# Sheet3.net
KiCad netlist of a schematic drawn in Altium Designer
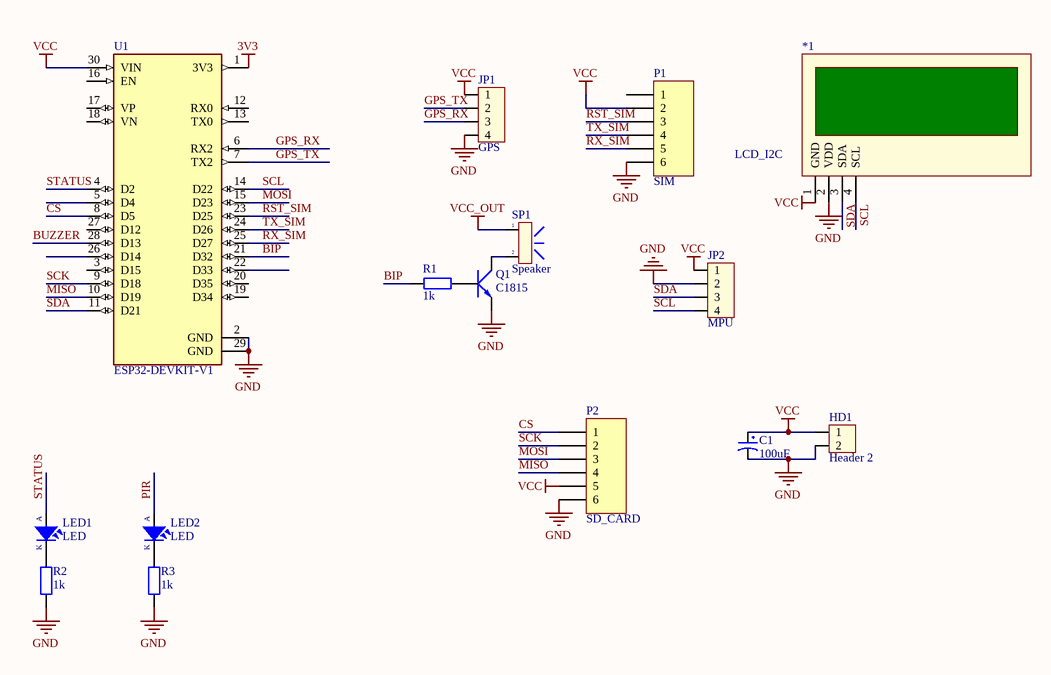
[diagram p0: Sheet3.SchDoc]

(export (version "E")
  (design (tool "Eeschema 10.0.6"))
  (components
    (comp (ref "*1")
      (value "LCD_I2C")
      (footprint "LCD_I2C_2004")
      (libsource (lib "LCD_i2c") (part "LCD_I2C"))
    )
    (comp (ref "C1")
      (value "100uF")
      (footprint "PART:CP1.5/3.4")
      (description "Cap 100uF/35V - 470uF/16V")
      (libsource (lib "PART") (part "CP3"))
    )
    (comp (ref "HD1")
      (value "Header 2")
      (footprint "PART:HED2")
      (description "Header 2 (Green)")
      (libsource (lib "PART") (part "Hed2"))
    )
    (comp (ref "JP1")
      (value "GPS")
      (footprint "CON4")
      (description "Connector 4")
      (libsource (lib "PART") (part "Con4"))
    )
    (comp (ref "JP2")
      (value "MPU")
      (footprint "CON4")
      (description "Connector 4")
      (libsource (lib "PART") (part "Con4"))
    )
    (comp (ref "LED1")
      (value "LED")
      (footprint "LED-5")
      (description "LED Single colour Green and Red")
      (libsource (lib "PART") (part "LED"))
    )
    (comp (ref "LED2")
      (value "LED")
      (footprint "LED-5")
      (description "LED Single colour Green and Red")
      (libsource (lib "PART") (part "LED"))
    )
    (comp (ref "P1")
      (value "SIM")
      (footprint "HDR1X6")
      (description "Header, 6-Pin")
      (fields (field (name "PUBLISHER") "Altium Limited"))
      (libsource (lib "Miscellaneous Connectors") (part "Header 6"))
    )
    (comp (ref "P2")
      (value "SD_CARD")
      (footprint "HDR1X6")
      (description "Header, 6-Pin")
      (fields (field (name "PUBLISHER") "Altium Limited"))
      (libsource (lib "Miscellaneous Connectors") (part "Header 6"))
    )
    (comp (ref "Q1")
      (value "C1815")
      (footprint "QTO-92")
      (description "NPN 600mW, ECB")
      (libsource (lib "PART") (part "C1815"))
    )
    (comp (ref "R1")
      (value "1k")
      (footprint "R1/4W")
      (description "Resistor 1/4W")
      (libsource (lib "PART") (part "R1/4W"))
    )
    (comp (ref "R2")
      (value "1k")
      (footprint "R1/4W")
      (description "Resistor 1/4W")
      (libsource (lib "PART") (part "R1/4W"))
    )
    (comp (ref "R3")
      (value "1k")
      (footprint "R1/4W")
      (description "Resistor 1/4W")
      (libsource (lib "PART") (part "R1/4W"))
    )
    (comp (ref "SP1")
      (value "Speaker")
      (footprint "SPK")
      (description "Speaker Chip")
      (libsource (lib "PART") (part "SPK"))
    )
    (comp (ref "U1")
      (value "ESP32-DEVKIT-V1")
      (footprint "MODULE_ESP32_DEVKIT_V1")
      (fields (field (name "MF") "Do it"))
      (libsource (lib "ESP32-DEVKIT-V1") (part "ESP32-DEVKIT-V1"))
    )
  )
  (nets
    (net (code "1") (name "/BIP") (class "Default")
      (node (ref "R1") (pin "2") (pinfunction "2_2") (pintype "passive"))
      (node (ref "U1") (pin "21") (pinfunction "D32_21") (pintype "bidirectional"))
    )
    (net (code "2") (name "/BUZZER") (class "Default")
      (node (ref "U1") (pin "28") (pinfunction "D13_28") (pintype "bidirectional"))
    )
    (net (code "3") (name "/CS") (class "Default")
      (node (ref "P2") (pin "1") (pinfunction "1_1") (pintype "passive"))
      (node (ref "U1") (pin "8") (pinfunction "D5_8") (pintype "bidirectional"))
    )
    (net (code "4") (name "/GPS_RX") (class "Default")
      (node (ref "JP1") (pin "3") (pinfunction "3_3") (pintype "passive"))
      (node (ref "U1") (pin "6") (pinfunction "RX2_6") (pintype "input"))
    )
    (net (code "5") (name "/GPS_TX") (class "Default")
      (node (ref "JP1") (pin "2") (pinfunction "2_2") (pintype "passive"))
      (node (ref "U1") (pin "7") (pinfunction "TX2_7") (pintype "output"))
    )
    (net (code "6") (name "/MISO") (class "Default")
      (node (ref "P2") (pin "4") (pinfunction "4_4") (pintype "passive"))
      (node (ref "U1") (pin "10") (pinfunction "D19_10") (pintype "bidirectional"))
    )
    (net (code "7") (name "/MOSI") (class "Default")
      (node (ref "P2") (pin "3") (pinfunction "3_3") (pintype "passive"))
      (node (ref "U1") (pin "15") (pinfunction "D23_15") (pintype "bidirectional"))
    )
    (net (code "8") (name "/PIR") (class "Default")
      (node (ref "LED2") (pin "1") (pinfunction "A_1") (pintype "passive"))
    )
    (net (code "9") (name "/RST_SIM") (class "Default")
      (node (ref "P1") (pin "3") (pinfunction "3_3") (pintype "passive"))
      (node (ref "U1") (pin "23") (pinfunction "D25_23") (pintype "bidirectional"))
    )
    (net (code "10") (name "/RX_SIM") (class "Default")
      (node (ref "P1") (pin "5") (pinfunction "5_5") (pintype "passive"))
      (node (ref "U1") (pin "25") (pinfunction "D27_25") (pintype "bidirectional"))
    )
    (net (code "11") (name "/SCK") (class "Default")
      (node (ref "P2") (pin "2") (pinfunction "2_2") (pintype "passive"))
      (node (ref "U1") (pin "9") (pinfunction "D18_9") (pintype "bidirectional"))
    )
    (net (code "12") (name "/SCL") (class "Default")
      (node (ref "*1") (pin "4") (pinfunction "SCL_4") (pintype "passive"))
      (node (ref "JP2") (pin "4") (pinfunction "4_4") (pintype "passive"))
      (node (ref "U1") (pin "14") (pinfunction "D22_14") (pintype "bidirectional"))
    )
    (net (code "13") (name "/SDA") (class "Default")
      (node (ref "*1") (pin "3") (pinfunction "SDA_3") (pintype "passive"))
      (node (ref "JP2") (pin "3") (pinfunction "3_3") (pintype "passive"))
      (node (ref "U1") (pin "11") (pinfunction "D21_11") (pintype "bidirectional"))
    )
    (net (code "14") (name "/STATUS") (class "Default")
      (node (ref "LED1") (pin "1") (pinfunction "A_1") (pintype "passive"))
      (node (ref "U1") (pin "4") (pinfunction "D2_4") (pintype "bidirectional"))
    )
    (net (code "15") (name "/TX_SIM") (class "Default")
      (node (ref "P1") (pin "4") (pinfunction "4_4") (pintype "passive"))
      (node (ref "U1") (pin "24") (pinfunction "D26_24") (pintype "bidirectional"))
    )
    (net (code "16") (name "3V3") (class "Default")
      (node (ref "U1") (pin "1") (pinfunction "3V3_1") (pintype "output"))
    )
    (net (code "17") (name "GND") (class "Default")
      (node (ref "*1") (pin "2") (pinfunction "VDD_2") (pintype "passive"))
      (node (ref "C1") (pin "2") (pinfunction "2_2") (pintype "passive"))
      (node (ref "HD1") (pin "2") (pinfunction "2_2") (pintype "passive"))
      (node (ref "JP1") (pin "4") (pinfunction "4_4") (pintype "passive"))
      (node (ref "JP2") (pin "2") (pinfunction "2_2") (pintype "passive"))
      (node (ref "P1") (pin "6") (pinfunction "6_6") (pintype "passive"))
      (node (ref "P2") (pin "6") (pinfunction "6_6") (pintype "passive"))
      (node (ref "Q1") (pin "1") (pinfunction "E_1") (pintype "passive"))
      (node (ref "R2") (pin "1") (pinfunction "1_1") (pintype "passive"))
      (node (ref "R3") (pin "1") (pinfunction "1_1") (pintype "passive"))
      (node (ref "U1") (pin "2") (pinfunction "GND_2") (pintype "power_in"))
      (node (ref "U1") (pin "29") (pinfunction "GND_29") (pintype "power_in"))
    )
    (net (code "18") (name "Net-(LED1-K)") (class "Default")
      (node (ref "LED1") (pin "2") (pinfunction "K_2") (pintype "passive"))
      (node (ref "R2") (pin "2") (pinfunction "2_2") (pintype "passive"))
    )
    (net (code "19") (name "Net-(LED2-K)") (class "Default")
      (node (ref "LED2") (pin "2") (pinfunction "K_2") (pintype "passive"))
      (node (ref "R3") (pin "2") (pinfunction "2_2") (pintype "passive"))
    )
    (net (code "20") (name "Net-(Q1-B)") (class "Default")
      (node (ref "Q1") (pin "3") (pinfunction "B_3") (pintype "passive"))
      (node (ref "R1") (pin "1") (pinfunction "1_1") (pintype "passive"))
    )
    (net (code "21") (name "Net-(Q1-C)") (class "Default")
      (node (ref "Q1") (pin "2") (pinfunction "C_2") (pintype "passive"))
      (node (ref "SP1") (pin "2") (pinfunction "2_2") (pintype "passive"))
    )
    (net (code "22") (name "VCC") (class "Default")
      (node (ref "*1") (pin "1") (pinfunction "GND_1") (pintype "passive"))
      (node (ref "C1") (pin "1") (pinfunction "1_1") (pintype "passive"))
      (node (ref "HD1") (pin "1") (pinfunction "1_1") (pintype "passive"))
      (node (ref "JP1") (pin "1") (pinfunction "1_1") (pintype "passive"))
      (node (ref "JP2") (pin "1") (pinfunction "1_1") (pintype "passive"))
      (node (ref "P1") (pin "2") (pinfunction "2_2") (pintype "passive"))
      (node (ref "P2") (pin "5") (pinfunction "5_5") (pintype "passive"))
      (node (ref "U1") (pin "30") (pinfunction "VIN_30") (pintype "input"))
    )
    (net (code "23") (name "VCC_OUT") (class "Default")
      (node (ref "SP1") (pin "1") (pinfunction "1_1") (pintype "passive"))
    )
    (net (code "24") (name "unconnected-(P1-Pad1)") (class "Default")
      (node (ref "P1") (pin "1") (pinfunction "1_1") (pintype "passive"))
    )
    (net (code "25") (name "unconnected-(U1-D4-Pad5)") (class "Default")
      (node (ref "U1") (pin "5") (pinfunction "D4_5") (pintype "bidirectional"))
    )
    (net (code "26") (name "unconnected-(U1-D12-Pad27)") (class "Default")
      (node (ref "U1") (pin "27") (pinfunction "D12_27") (pintype "bidirectional"))
    )
    (net (code "27") (name "unconnected-(U1-D14-Pad26)") (class "Default")
      (node (ref "U1") (pin "26") (pinfunction "D14_26") (pintype "bidirectional"))
    )
    (net (code "28") (name "unconnected-(U1-D15-Pad3)") (class "Default")
      (node (ref "U1") (pin "3") (pinfunction "D15_3") (pintype "bidirectional"))
    )
    (net (code "29") (name "unconnected-(U1-D33-Pad22)") (class "Default")
      (node (ref "U1") (pin "22") (pinfunction "D33_22") (pintype "bidirectional"))
    )
    (net (code "30") (name "unconnected-(U1-D34-Pad19)") (class "Default")
      (node (ref "U1") (pin "19") (pinfunction "D34_19") (pintype "bidirectional"))
    )
    (net (code "31") (name "unconnected-(U1-D35-Pad20)") (class "Default")
      (node (ref "U1") (pin "20") (pinfunction "D35_20") (pintype "bidirectional"))
    )
    (net (code "32") (name "unconnected-(U1-EN-Pad16)") (class "Default")
      (node (ref "U1") (pin "16") (pinfunction "EN_16") (pintype "input"))
    )
    (net (code "33") (name "unconnected-(U1-RX0-Pad12)") (class "Default")
      (node (ref "U1") (pin "12") (pinfunction "RX0_12") (pintype "input"))
    )
    (net (code "34") (name "unconnected-(U1-TX0-Pad13)") (class "Default")
      (node (ref "U1") (pin "13") (pinfunction "TX0_13") (pintype "output"))
    )
    (net (code "35") (name "unconnected-(U1-VN-Pad18)") (class "Default")
      (node (ref "U1") (pin "18") (pinfunction "VN_18") (pintype "bidirectional"))
    )
    (net (code "36") (name "unconnected-(U1-VP-Pad17)") (class "Default")
      (node (ref "U1") (pin "17") (pinfunction "VP_17") (pintype "bidirectional"))
    )
  )
)
